# Power.net
KiCad netlist of a schematic drawn in Altium Designer
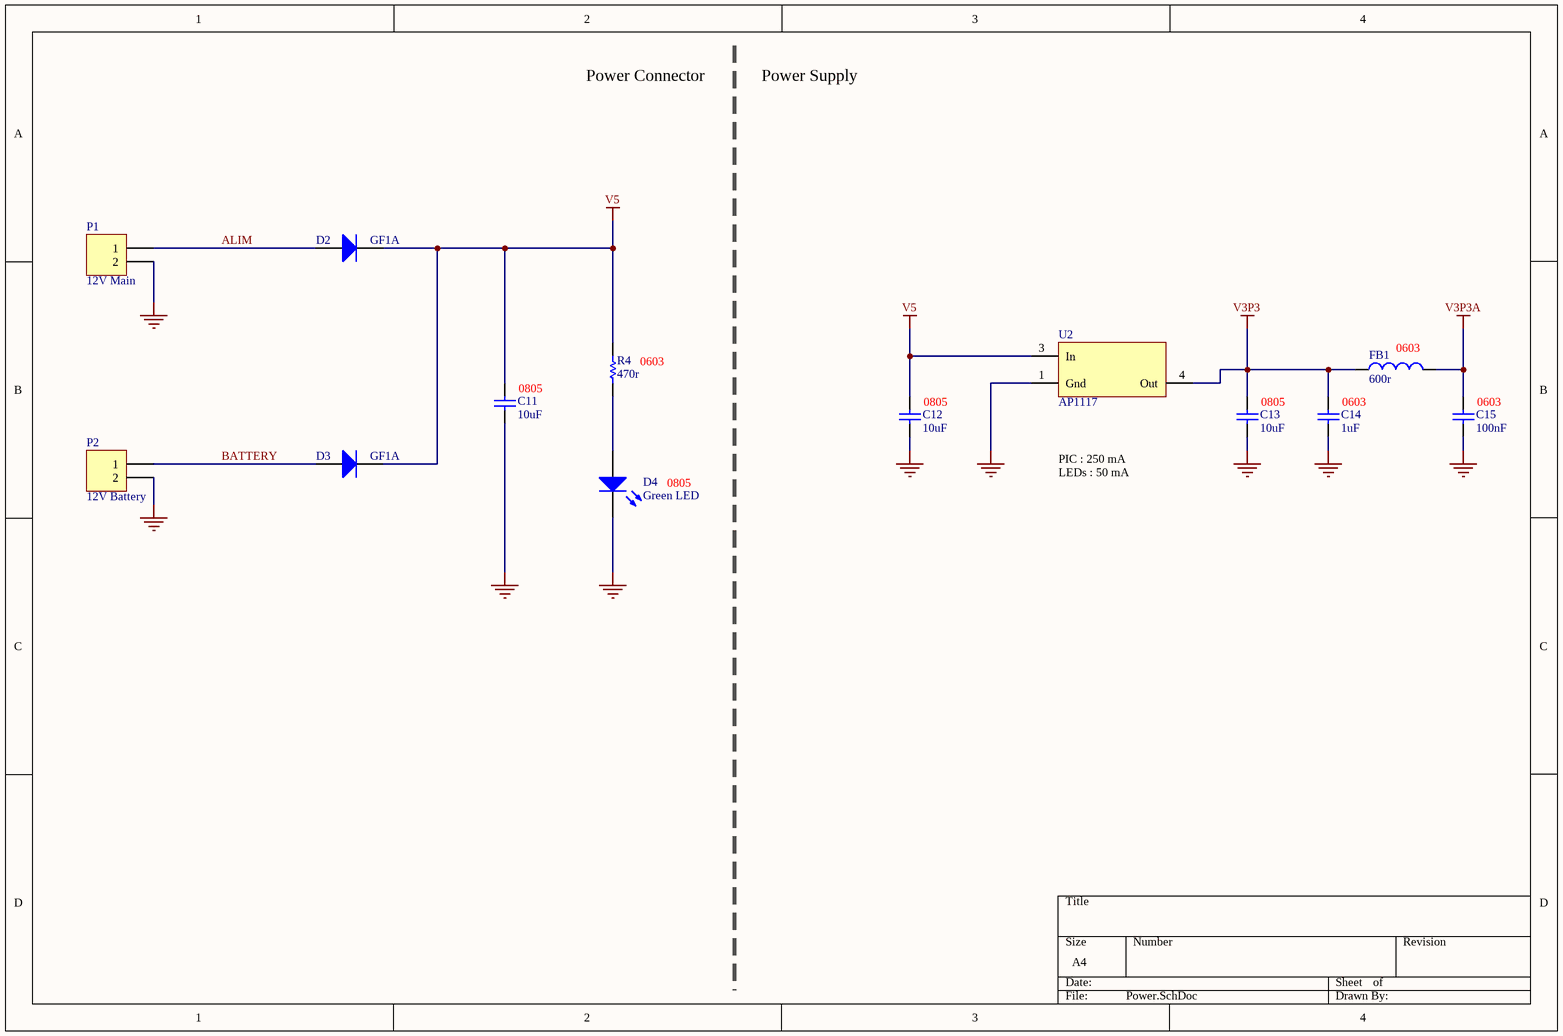
[diagram p0: Power.SchDoc]

(export (version "E")
  (design (tool "Eeschema 10.0.6"))
  (components
    (comp (ref "C11")
      (value "10uF")
      (footprint "0805")
      (description "Capacitor")
      (fields (field (name "PUBLISHER") "Altium Limited"))
      (libsource (lib "Miscellaneous Devices") (part "Cap"))
    )
    (comp (ref "C12")
      (value "10uF")
      (footprint "0805")
      (description "Capacitor")
      (fields (field (name "PUBLISHER") "Altium Limited"))
      (libsource (lib "Miscellaneous Devices") (part "Cap"))
    )
    (comp (ref "C13")
      (value "10uF")
      (footprint "0805")
      (description "Capacitor")
      (fields (field (name "PUBLISHER") "Altium Limited"))
      (libsource (lib "Miscellaneous Devices") (part "Cap"))
    )
    (comp (ref "C14")
      (value "1uF")
      (footprint "0603")
      (description "Capacitor")
      (fields (field (name "PUBLISHER") "Altium Limited"))
      (libsource (lib "Miscellaneous Devices") (part "Cap"))
    )
    (comp (ref "C15")
      (value "100nF")
      (footprint "0603")
      (description "Capacitor")
      (fields (field (name "PUBLISHER") "Altium Limited"))
      (libsource (lib "Miscellaneous Devices") (part "Cap"))
    )
    (comp (ref "D2")
      (value "GF1A")
      (footprint "TP2_PcbLib:SMA/DO-214AC_21")
      (description "Default Diode")
      (fields (field (name "PUBLISHER") "Altium Limited"))
      (libsource (lib "Miscellaneous Devices") (part "Diode"))
    )
    (comp (ref "D3")
      (value "GF1A")
      (footprint "TP2_PcbLib:SMA/DO-214AC_21")
      (description "Default Diode")
      (fields (field (name "PUBLISHER") "Altium Limited"))
      (libsource (lib "Miscellaneous Devices") (part "Diode"))
    )
    (comp (ref "D4")
      (value "Green LED")
      (footprint "0805")
      (description "Typical INFRARED GaAs LED")
      (fields (field (name "PUBLISHER") "Altium Limited"))
      (libsource (lib "Miscellaneous Devices") (part "LED2"))
    )
    (comp (ref "FB1")
      (value "600r")
      (footprint "0603")
      (description "Ferrite Bead")
      (fields (field (name "PUBLISHER") "Altium Limited"))
      (libsource (lib "Miscellaneous Devices") (part "Inductor"))
    )
    (comp (ref "P1")
      (value "12V Main")
      (footprint "TP2_PcbLib:PHOENIX_1985195")
      (description "Header, 2-Pin")
      (fields (field (name "PUBLISHER") "Altium Limited"))
      (libsource (lib "Miscellaneous Connectors") (part "Header 2"))
    )
    (comp (ref "P2")
      (value "12V Battery")
      (footprint "TP2_PcbLib:PHOENIX_1985195")
      (description "Header, 2-Pin")
      (fields (field (name "PUBLISHER") "Altium Limited"))
      (libsource (lib "Miscellaneous Connectors") (part "Header 2"))
    )
    (comp (ref "R4")
      (value "470r")
      (footprint "0603")
      (description "Resistor")
      (fields (field (name "PUBLISHER") "Altium Limited"))
      (libsource (lib "Miscellaneous Devices") (part "Res1"))
    )
    (comp (ref "U2")
      (value "AP1117")
      (footprint "TP2_PcbLib:TD03B_N")
      (description "1A LDO, 18V input, DPAK")
      (libsource (lib "regulator") (part "AP1117"))
    )
  )
  (nets
    (net (code "1") (name "/ALIM") (class "Default")
      (node (ref "D2") (pin "1") (pinfunction "A_1") (pintype "passive"))
      (node (ref "P1") (pin "1") (pinfunction "1_1") (pintype "passive"))
    )
    (net (code "2") (name "/BATTERY") (class "Default")
      (node (ref "D3") (pin "1") (pinfunction "A_1") (pintype "passive"))
      (node (ref "P2") (pin "1") (pinfunction "1_1") (pintype "passive"))
    )
    (net (code "3") (name "GND") (class "Default")
      (node (ref "C11") (pin "1") (pinfunction "1_1") (pintype "passive"))
      (node (ref "C12") (pin "1") (pinfunction "1_1") (pintype "passive"))
      (node (ref "C13") (pin "1") (pinfunction "1_1") (pintype "passive"))
      (node (ref "C14") (pin "1") (pinfunction "1_1") (pintype "passive"))
      (node (ref "C15") (pin "1") (pinfunction "1_1") (pintype "passive"))
      (node (ref "D4") (pin "2") (pinfunction "K_2") (pintype "passive"))
      (node (ref "P1") (pin "2") (pinfunction "2_2") (pintype "passive"))
      (node (ref "P2") (pin "2") (pinfunction "2_2") (pintype "passive"))
      (node (ref "U2") (pin "1") (pinfunction "Gnd_1") (pintype "passive"))
    )
    (net (code "4") (name "Net-(D4-A)") (class "Default")
      (node (ref "D4") (pin "1") (pinfunction "A_1") (pintype "passive"))
      (node (ref "R4") (pin "1") (pinfunction "1_1") (pintype "passive"))
    )
    (net (code "5") (name "V3P3") (class "Default")
      (node (ref "C13") (pin "2") (pinfunction "2_2") (pintype "passive"))
      (node (ref "C14") (pin "2") (pinfunction "2_2") (pintype "passive"))
      (node (ref "FB1") (pin "1") (pinfunction "1_1") (pintype "passive"))
      (node (ref "U2") (pin "4") (pinfunction "Out_4") (pintype "passive"))
    )
    (net (code "6") (name "V3P3A") (class "Default")
      (node (ref "C15") (pin "2") (pinfunction "2_2") (pintype "passive"))
      (node (ref "FB1") (pin "2") (pinfunction "2_2") (pintype "passive"))
    )
    (net (code "7") (name "V5") (class "Default")
      (node (ref "C11") (pin "2") (pinfunction "2_2") (pintype "passive"))
      (node (ref "C12") (pin "2") (pinfunction "2_2") (pintype "passive"))
      (node (ref "D2") (pin "2") (pinfunction "K_2") (pintype "passive"))
      (node (ref "D3") (pin "2") (pinfunction "K_2") (pintype "passive"))
      (node (ref "R4") (pin "2") (pinfunction "2_2") (pintype "passive"))
      (node (ref "U2") (pin "3") (pinfunction "In_3") (pintype "passive"))
    )
  )
)
